# TestBench_rev2.net
KiCad netlist of a schematic drawn in EAGLE
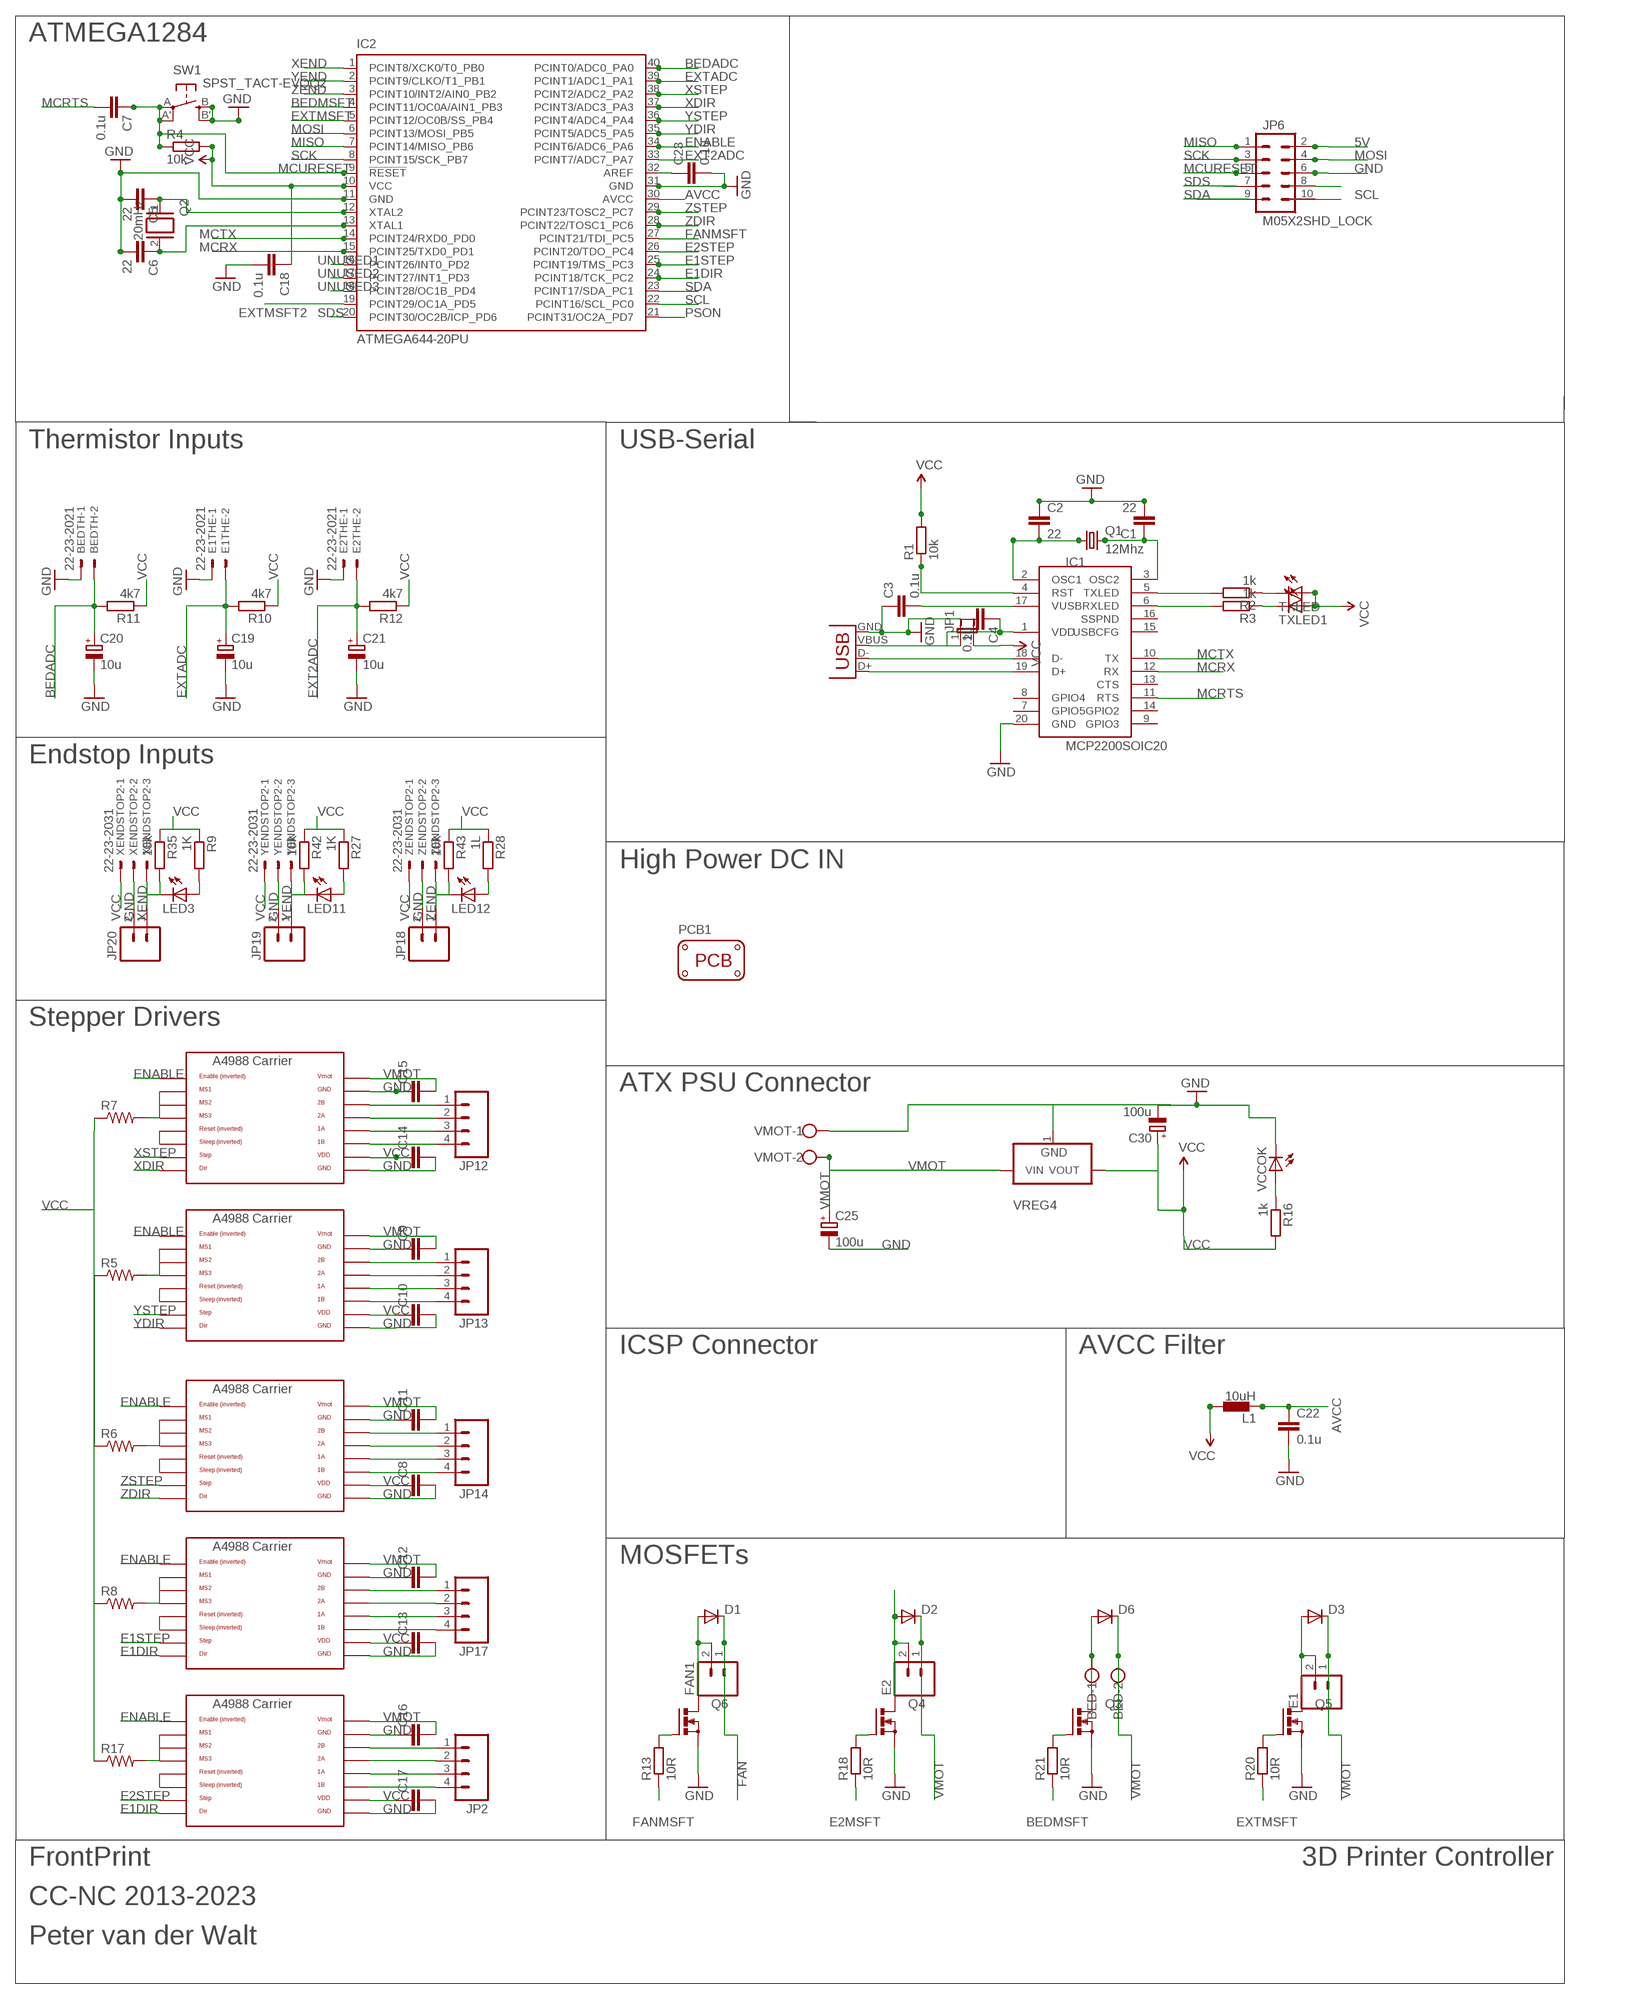
[diagram p0: schematic, sheet 1]

(export (version "E")
  (design (tool "Eeschema 10.0.6"))
  (components
    (comp (ref "BED")
      (value "W237-102")
      (footprint "eagle-import:W237-102")
      (fields (field (name "MPN") "237-102"))
      (libsource (lib "eagle-import") (part "W237-102"))
    )
    (comp (ref "BEDTH")
      (value "22-23-2021")
      (footprint "eagle-import:22-23-2021")
      (fields (field (name "MF") "MOLEX"))
      (libsource (lib "eagle-import") (part "22-23-2021"))
    )
    (comp (ref "C1")
      (value "22")
      (footprint "eagle-import:1206")
      (libsource (lib "eagle-import") (part "CAP1206"))
    )
    (comp (ref "C2")
      (value "22")
      (footprint "eagle-import:1206")
      (libsource (lib "eagle-import") (part "CAP1206"))
    )
    (comp (ref "C3")
      (value "0.1u")
      (footprint "eagle-import:1206")
      (libsource (lib "eagle-import") (part "CAP1206"))
    )
    (comp (ref "C4")
      (value "0.1u")
      (footprint "eagle-import:1206")
      (libsource (lib "eagle-import") (part "CAP1206"))
    )
    (comp (ref "C5")
      (value "22")
      (footprint "eagle-import:1206")
      (libsource (lib "eagle-import") (part "CAP1206"))
    )
    (comp (ref "C6")
      (value "22")
      (footprint "eagle-import:1206")
      (libsource (lib "eagle-import") (part "CAP1206"))
    )
    (comp (ref "C7")
      (value "0.1u")
      (footprint "eagle-import:1206")
      (libsource (lib "eagle-import") (part "CAP1206"))
    )
    (comp (ref "C8")
      (value "CAP1206")
      (footprint "eagle-import:1206")
      (libsource (lib "eagle-import") (part "CAP1206"))
    )
    (comp (ref "C9")
      (value "CAP1206")
      (footprint "eagle-import:1206")
      (libsource (lib "eagle-import") (part "CAP1206"))
    )
    (comp (ref "C10")
      (value "CAP1206")
      (footprint "eagle-import:1206")
      (libsource (lib "eagle-import") (part "CAP1206"))
    )
    (comp (ref "C11")
      (value "CAP1206")
      (footprint "eagle-import:1206")
      (libsource (lib "eagle-import") (part "CAP1206"))
    )
    (comp (ref "C12")
      (value "CAP1206")
      (footprint "eagle-import:1206")
      (libsource (lib "eagle-import") (part "CAP1206"))
    )
    (comp (ref "C13")
      (value "CAP1206")
      (footprint "eagle-import:1206")
      (libsource (lib "eagle-import") (part "CAP1206"))
    )
    (comp (ref "C14")
      (value "CAP1206")
      (footprint "eagle-import:1206")
      (libsource (lib "eagle-import") (part "CAP1206"))
    )
    (comp (ref "C15")
      (value "CAP1206")
      (footprint "eagle-import:1206")
      (libsource (lib "eagle-import") (part "CAP1206"))
    )
    (comp (ref "C16")
      (value "CAP1206")
      (footprint "eagle-import:1206")
      (libsource (lib "eagle-import") (part "CAP1206"))
    )
    (comp (ref "C17")
      (value "CAP1206")
      (footprint "eagle-import:1206")
      (libsource (lib "eagle-import") (part "CAP1206"))
    )
    (comp (ref "C18")
      (value "0.1u")
      (footprint "eagle-import:1206")
      (libsource (lib "eagle-import") (part "CAP1206"))
    )
    (comp (ref "C19")
      (value "10u")
      (footprint "eagle-import:E2,5-5")
      (libsource (lib "eagle-import") (part "CPOL-EUE2.5-5"))
    )
    (comp (ref "C20")
      (value "10u")
      (footprint "eagle-import:E2,5-5")
      (libsource (lib "eagle-import") (part "CPOL-EUE2.5-5"))
    )
    (comp (ref "C21")
      (value "10u")
      (footprint "eagle-import:E2,5-5")
      (libsource (lib "eagle-import") (part "CPOL-EUE2.5-5"))
    )
    (comp (ref "C22")
      (value "0.1u")
      (footprint "eagle-import:1206")
      (libsource (lib "eagle-import") (part "CAP1206"))
    )
    (comp (ref "C23")
      (value "0.1u")
      (footprint "eagle-import:1206")
      (libsource (lib "eagle-import") (part "CAP1206"))
    )
    (comp (ref "C25")
      (value "100u")
      (footprint "eagle-import:E5-8,5")
      (libsource (lib "eagle-import") (part "CPOL-EUE5-8.5"))
    )
    (comp (ref "C30")
      (value "100u")
      (footprint "eagle-import:E5-8,5")
      (libsource (lib "eagle-import") (part "CPOL-EUE5-8.5"))
    )
    (comp (ref "D1")
      (value "DIODE1N4148")
      (footprint "eagle-import:DIODE-1N4148")
      (libsource (lib "eagle-import") (part "DIODE1N4148"))
    )
    (comp (ref "D2")
      (value "DIODE1N4148")
      (footprint "eagle-import:DIODE-1N4148")
      (libsource (lib "eagle-import") (part "DIODE1N4148"))
    )
    (comp (ref "D3")
      (value "DIODE1N4148")
      (footprint "eagle-import:DIODE-1N4148")
      (libsource (lib "eagle-import") (part "DIODE1N4148"))
    )
    (comp (ref "D6")
      (value "DIODE1N4148")
      (footprint "eagle-import:DIODE-1N4148")
      (libsource (lib "eagle-import") (part "DIODE1N4148"))
    )
    (comp (ref "E1")
      (value "M023.5MM")
      (footprint "eagle-import:SCREWTERMINAL-3.5MM-2")
      (libsource (lib "eagle-import") (part "M023.5MM"))
    )
    (comp (ref "E1POL")
      (value "POLOLU_A4983CARRIER")
      (footprint "eagle-import:A4988BREAKOUT")
      (libsource (lib "eagle-import") (part "POLOLU_A4983CARRIER"))
    )
    (comp (ref "E1THE")
      (value "22-23-2021")
      (footprint "eagle-import:22-23-2021")
      (fields (field (name "MF") "MOLEX"))
      (libsource (lib "eagle-import") (part "22-23-2021"))
    )
    (comp (ref "E2")
      (value "M023.5MM")
      (footprint "eagle-import:SCREWTERMINAL-3.5MM-2")
      (libsource (lib "eagle-import") (part "M023.5MM"))
    )
    (comp (ref "E2POL")
      (value "POLOLU_A4983CARRIER")
      (footprint "eagle-import:A4988BREAKOUT")
      (libsource (lib "eagle-import") (part "POLOLU_A4983CARRIER"))
    )
    (comp (ref "E2THE")
      (value "22-23-2021")
      (footprint "eagle-import:22-23-2021")
      (fields (field (name "MF") "MOLEX"))
      (libsource (lib "eagle-import") (part "22-23-2021"))
    )
    (comp (ref "FAN1")
      (value "M023.5MM")
      (footprint "eagle-import:SCREWTERMINAL-3.5MM-2")
      (libsource (lib "eagle-import") (part "M023.5MM"))
    )
    (comp (ref "IC1")
      (value "MCP2200SOIC20")
      (footprint "eagle-import:SOIC20")
      (libsource (lib "eagle-import") (part "MCP2200SOIC20"))
    )
    (comp (ref "IC2")
      (value "ATMEGA644-20PU")
      (footprint "eagle-import:DIL40")
      (libsource (lib "eagle-import") (part "ATMEGA644-PU20"))
    )
    (comp (ref "JP1")
      (value "JUMPER-2PTH_LOCK")
      (footprint "eagle-import:1X02_LOCK")
      (libsource (lib "eagle-import") (part "JUMPER-2PTH_LOCK"))
    )
    (comp (ref "JP2")
      (value "M04SCREW")
      (footprint "eagle-import:SCREWTERMINAL-3.5MM-4")
      (libsource (lib "eagle-import") (part "M04SCREW"))
    )
    (comp (ref "JP6")
      (value "M05X2SHD_LOCK")
      (footprint "eagle-import:2X5-SHROUDED_LOCK")
      (libsource (lib "eagle-import") (part "M05X2SHD_LOCK"))
    )
    (comp (ref "JP12")
      (value "M04SCREW")
      (footprint "eagle-import:SCREWTERMINAL-3.5MM-4")
      (libsource (lib "eagle-import") (part "M04SCREW"))
    )
    (comp (ref "JP13")
      (value "M04SCREW")
      (footprint "eagle-import:SCREWTERMINAL-3.5MM-4")
      (libsource (lib "eagle-import") (part "M04SCREW"))
    )
    (comp (ref "JP14")
      (value "M04SCREW")
      (footprint "eagle-import:SCREWTERMINAL-3.5MM-4")
      (libsource (lib "eagle-import") (part "M04SCREW"))
    )
    (comp (ref "JP17")
      (value "M04SCREW")
      (footprint "eagle-import:SCREWTERMINAL-3.5MM-4")
      (libsource (lib "eagle-import") (part "M04SCREW"))
    )
    (comp (ref "JP18")
      (value "M023.5MM")
      (footprint "eagle-import:SCREWTERMINAL-3.5MM-2")
      (libsource (lib "eagle-import") (part "M023.5MM"))
    )
    (comp (ref "JP19")
      (value "M023.5MM")
      (footprint "eagle-import:SCREWTERMINAL-3.5MM-2")
      (libsource (lib "eagle-import") (part "M023.5MM"))
    )
    (comp (ref "JP20")
      (value "M023.5MM")
      (footprint "eagle-import:SCREWTERMINAL-3.5MM-2")
      (libsource (lib "eagle-import") (part "M023.5MM"))
    )
    (comp (ref "L1")
      (value "10uH")
      (footprint "eagle-import:BL01RN1A")
      (libsource (lib "eagle-import") (part "BL01RN1A"))
    )
    (comp (ref "LED3")
      (value "LEDCHIPLED_1206")
      (footprint "eagle-import:CHIPLED_1206")
      (libsource (lib "eagle-import") (part "LEDCHIPLED_1206"))
    )
    (comp (ref "LED11")
      (value "LEDCHIPLED_1206")
      (footprint "eagle-import:CHIPLED_1206")
      (libsource (lib "eagle-import") (part "LEDCHIPLED_1206"))
    )
    (comp (ref "LED12")
      (value "LEDCHIPLED_1206")
      (footprint "eagle-import:CHIPLED_1206")
      (libsource (lib "eagle-import") (part "LEDCHIPLED_1206"))
    )
    (comp (ref "PCB1")
      (value "PCB_DP_SQUARE-10X10")
      (footprint "eagle-import:DP100100_V1")
      (libsource (lib "eagle-import") (part "PCB_DP_SQUARE-10X10"))
    )
    (comp (ref "Q1")
      (value "12Mhz")
      (footprint "eagle-import:HC49UP")
      (libsource (lib "eagle-import") (part "CRYSTALHC49UP"))
    )
    (comp (ref "Q2")
      (value "20mHz")
      (footprint "eagle-import:QS")
      (libsource (lib "eagle-import") (part "XTAL/S"))
    )
    (comp (ref "Q3")
      (value "PMOSFET_NTO220BV")
      (footprint "eagle-import:TO220BV")
      (libsource (lib "eagle-import") (part "PMOSFET_NTO220BV"))
    )
    (comp (ref "Q4")
      (value "PMOSFET_NTO220BV")
      (footprint "eagle-import:TO220BV")
      (libsource (lib "eagle-import") (part "PMOSFET_NTO220BV"))
    )
    (comp (ref "Q5")
      (value "PMOSFET_NTO220BV")
      (footprint "eagle-import:TO220BV")
      (libsource (lib "eagle-import") (part "PMOSFET_NTO220BV"))
    )
    (comp (ref "Q6")
      (value "PMOSFET_NTO220BV")
      (footprint "eagle-import:TO220BV")
      (libsource (lib "eagle-import") (part "PMOSFET_NTO220BV"))
    )
    (comp (ref "R1")
      (value "10k")
      (footprint "eagle-import:M1206")
      (libsource (lib "eagle-import") (part "R-EU_M1206"))
    )
    (comp (ref "R2")
      (value "1k")
      (footprint "eagle-import:M1206")
      (libsource (lib "eagle-import") (part "R-EU_M1206"))
    )
    (comp (ref "R3")
      (value "1k")
      (footprint "eagle-import:M1206")
      (libsource (lib "eagle-import") (part "R-EU_M1206"))
    )
    (comp (ref "R4")
      (value "10k")
      (footprint "eagle-import:M1206")
      (libsource (lib "eagle-import") (part "R-EU_M1206"))
    )
    (comp (ref "R5")
      (value "RESISTOR1206")
      (footprint "eagle-import:1206")
      (libsource (lib "eagle-import") (part "RESISTOR1206"))
    )
    (comp (ref "R6")
      (value "RESISTOR1206")
      (footprint "eagle-import:1206")
      (libsource (lib "eagle-import") (part "RESISTOR1206"))
    )
    (comp (ref "R7")
      (value "RESISTOR1206")
      (footprint "eagle-import:1206")
      (libsource (lib "eagle-import") (part "RESISTOR1206"))
    )
    (comp (ref "R8")
      (value "RESISTOR1206")
      (footprint "eagle-import:1206")
      (libsource (lib "eagle-import") (part "RESISTOR1206"))
    )
    (comp (ref "R9")
      (value "1K")
      (footprint "eagle-import:M1206")
      (libsource (lib "eagle-import") (part "R-EU_M1206"))
    )
    (comp (ref "R10")
      (value "4k7")
      (footprint "eagle-import:M1206")
      (libsource (lib "eagle-import") (part "R-EU_M1206"))
    )
    (comp (ref "R11")
      (value "4k7")
      (footprint "eagle-import:M1206")
      (libsource (lib "eagle-import") (part "R-EU_M1206"))
    )
    (comp (ref "R12")
      (value "4k7")
      (footprint "eagle-import:M1206")
      (libsource (lib "eagle-import") (part "R-EU_M1206"))
    )
    (comp (ref "R13")
      (value "10R")
      (footprint "eagle-import:M1206")
      (libsource (lib "eagle-import") (part "R-EU_M1206"))
    )
    (comp (ref "R16")
      (value "1k")
      (footprint "eagle-import:M1206")
      (libsource (lib "eagle-import") (part "R-EU_M1206"))
    )
    (comp (ref "R17")
      (value "RESISTOR1206")
      (footprint "eagle-import:1206")
      (libsource (lib "eagle-import") (part "RESISTOR1206"))
    )
    (comp (ref "R18")
      (value "10R")
      (footprint "eagle-import:M1206")
      (libsource (lib "eagle-import") (part "R-EU_M1206"))
    )
    (comp (ref "R20")
      (value "10R")
      (footprint "eagle-import:M1206")
      (libsource (lib "eagle-import") (part "R-EU_M1206"))
    )
    (comp (ref "R21")
      (value "10R")
      (footprint "eagle-import:M1206")
      (libsource (lib "eagle-import") (part "R-EU_M1206"))
    )
    (comp (ref "R27")
      (value "1K")
      (footprint "eagle-import:M1206")
      (libsource (lib "eagle-import") (part "R-EU_M1206"))
    )
    (comp (ref "R28")
      (value "1L")
      (footprint "eagle-import:M1206")
      (libsource (lib "eagle-import") (part "R-EU_M1206"))
    )
    (comp (ref "R35")
      (value "10k")
      (footprint "eagle-import:M1206")
      (libsource (lib "eagle-import") (part "R-EU_M1206"))
    )
    (comp (ref "R42")
      (value "10k")
      (footprint "eagle-import:M1206")
      (libsource (lib "eagle-import") (part "R-EU_M1206"))
    )
    (comp (ref "R43")
      (value "10k")
      (footprint "eagle-import:M1206")
      (libsource (lib "eagle-import") (part "R-EU_M1206"))
    )
    (comp (ref "SW1")
      (value "SPST_TACT-EVQQ2")
      (footprint "eagle-import:EVQ-Q2")
      (libsource (lib "eagle-import") (part "SPST_TACT-EVQQ2"))
    )
    (comp (ref "TXLED")
      (value "LEDSMT1206")
      (footprint "eagle-import:1206")
      (libsource (lib "eagle-import") (part "LEDSMT1206"))
    )
    (comp (ref "TXLED1")
      (value "LEDSMT1206")
      (footprint "eagle-import:1206")
      (libsource (lib "eagle-import") (part "LEDSMT1206"))
    )
    (comp (ref "VCCOK")
      (value "LEDSMT1206")
      (footprint "eagle-import:1206")
      (libsource (lib "eagle-import") (part "LEDSMT1206"))
    )
    (comp (ref "VMOT")
      (value "W237-102")
      (footprint "eagle-import:W237-102")
      (fields
        (field (name "MPN") "237-102")
        (field (name "MPN_1") "237-102")
        (field (name "OC_FARNELL") "unknown")
        (field (name "OC_NEWARK") "70K9898")
      )
      (libsource (lib "eagle-import") (part "W237-102"))
    )
    (comp (ref "VREG4")
      (value "VREG_3PINS-DPAK")
      (footprint "eagle-import:DPAK")
      (libsource (lib "eagle-import") (part "VREG_3PINS-DPAK"))
    )
    (comp (ref "X1")
      (value "USBPTH")
      (footprint "eagle-import:USB-B-PTH")
      (libsource (lib "eagle-import") (part "USBPTH"))
    )
    (comp (ref "XENDSTOP2")
      (value "22-23-2031")
      (footprint "eagle-import:22-23-2031")
      (fields (field (name "MF") "MOLEX"))
      (libsource (lib "eagle-import") (part "22-23-2031"))
    )
    (comp (ref "XPOL")
      (value "POLOLU_A4983CARRIER")
      (footprint "eagle-import:A4988BREAKOUT")
      (libsource (lib "eagle-import") (part "POLOLU_A4983CARRIER"))
    )
    (comp (ref "YENDSTOP2")
      (value "22-23-2031")
      (footprint "eagle-import:22-23-2031")
      (fields (field (name "MF") "MOLEX"))
      (libsource (lib "eagle-import") (part "22-23-2031"))
    )
    (comp (ref "YPOL")
      (value "POLOLU_A4983CARRIER")
      (footprint "eagle-import:A4988BREAKOUT")
      (libsource (lib "eagle-import") (part "POLOLU_A4983CARRIER"))
    )
    (comp (ref "ZENDSTOP2")
      (value "22-23-2031")
      (footprint "eagle-import:22-23-2031")
      (fields (field (name "MF") "MOLEX"))
      (libsource (lib "eagle-import") (part "22-23-2031"))
    )
    (comp (ref "ZPOL")
      (value "POLOLU_A4983CARRIER")
      (footprint "eagle-import:A4988BREAKOUT")
      (libsource (lib "eagle-import") (part "POLOLU_A4983CARRIER"))
    )
  )
  (nets
    (net (code "1") (name "/5V") (class "Default")
      (node (ref "JP6") (pin "2") (pinfunction "2_2") (pintype "passive"))
    )
    (net (code "2") (name "/AVCC") (class "Default")
      (node (ref "C22") (pin "1") (pinfunction "1_1") (pintype "passive"))
      (node (ref "IC2") (pin "30") (pinfunction "AVCC_30") (pintype "power_in"))
      (node (ref "L1") (pin "1") (pinfunction "1_1") (pintype "passive"))
    )
    (net (code "3") (name "/BEDADC") (class "Default")
      (node (ref "BEDTH") (pin "2") (pinfunction "S_2") (pintype "passive"))
      (node (ref "C20") (pin "+") (pinfunction "+_+") (pintype "passive"))
      (node (ref "IC2") (pin "40") (pinfunction "PCINT0/ADC0_PA0_40") (pintype "bidirectional"))
      (node (ref "R11") (pin "2") (pinfunction "2_2") (pintype "passive"))
    )
    (net (code "4") (name "/BEDMSFT") (class "Default")
      (node (ref "IC2") (pin "4") (pinfunction "PCINT11/OC0A/AIN1_PB3_4") (pintype "bidirectional"))
      (node (ref "R21") (pin "1") (pinfunction "1_1") (pintype "passive"))
    )
    (net (code "5") (name "/E1DIR") (class "Default")
      (node (ref "E1POL") (pin "DIR") (pinfunction "DIR_DIR") (pintype "input"))
      (node (ref "E2POL") (pin "DIR") (pinfunction "DIR_DIR") (pintype "input"))
      (node (ref "IC2") (pin "24") (pinfunction "PCINT18/TCK_PC2_24") (pintype "bidirectional"))
    )
    (net (code "6") (name "/E1STEP") (class "Default")
      (node (ref "E1POL") (pin "STEP") (pinfunction "STEP_STEP") (pintype "input"))
      (node (ref "IC2") (pin "25") (pinfunction "PCINT19/TMS_PC3_25") (pintype "bidirectional"))
    )
    (net (code "7") (name "/E2MSFT") (class "Default")
      (node (ref "R18") (pin "1") (pinfunction "1_1") (pintype "passive"))
    )
    (net (code "8") (name "/E2STEP") (class "Default")
      (node (ref "E2POL") (pin "STEP") (pinfunction "STEP_STEP") (pintype "input"))
      (node (ref "IC2") (pin "26") (pinfunction "PCINT20/TDO_PC4_26") (pintype "bidirectional"))
    )
    (net (code "9") (name "/ENABLE") (class "Default")
      (node (ref "E1POL") (pin "EN") (pinfunction "EN_EN") (pintype "input"))
      (node (ref "E2POL") (pin "EN") (pinfunction "EN_EN") (pintype "input"))
      (node (ref "IC2") (pin "34") (pinfunction "PCINT6/ADC6_PA6_34") (pintype "bidirectional"))
      (node (ref "XPOL") (pin "EN") (pinfunction "EN_EN") (pintype "input"))
      (node (ref "YPOL") (pin "EN") (pinfunction "EN_EN") (pintype "input"))
      (node (ref "ZPOL") (pin "EN") (pinfunction "EN_EN") (pintype "input"))
    )
    (net (code "10") (name "/EXT2ADC") (class "Default")
      (node (ref "C21") (pin "+") (pinfunction "+_+") (pintype "passive"))
      (node (ref "E2THE") (pin "2") (pinfunction "S_2") (pintype "passive"))
      (node (ref "IC2") (pin "33") (pinfunction "PCINT7/ADC7_PA7_33") (pintype "bidirectional"))
      (node (ref "R12") (pin "2") (pinfunction "2_2") (pintype "passive"))
    )
    (net (code "11") (name "/EXTADC") (class "Default")
      (node (ref "C19") (pin "+") (pinfunction "+_+") (pintype "passive"))
      (node (ref "E1THE") (pin "2") (pinfunction "S_2") (pintype "passive"))
      (node (ref "IC2") (pin "39") (pinfunction "PCINT1/ADC1_PA1_39") (pintype "bidirectional"))
      (node (ref "R10") (pin "2") (pinfunction "2_2") (pintype "passive"))
    )
    (net (code "12") (name "/EXTMSFT") (class "Default")
      (node (ref "IC2") (pin "5") (pinfunction "PCINT12/OC0B/SS_PB4_5") (pintype "bidirectional"))
      (node (ref "R20") (pin "1") (pinfunction "1_1") (pintype "passive"))
    )
    (net (code "13") (name "/EXTMSFT2") (class "Default")
      (node (ref "IC2") (pin "19") (pinfunction "PCINT29/OC1A_PD5_19") (pintype "bidirectional"))
    )
    (net (code "14") (name "/FAN") (class "Default")
      (node (ref "D1") (pin "C") (pinfunction "C_C") (pintype "passive"))
      (node (ref "FAN1") (pin "1") (pinfunction "1_1") (pintype "passive"))
    )
    (net (code "15") (name "/FANMSFT") (class "Default")
      (node (ref "IC2") (pin "27") (pinfunction "PCINT21/TDI_PC5_27") (pintype "bidirectional"))
      (node (ref "R13") (pin "1") (pinfunction "1_1") (pintype "passive"))
    )
    (net (code "16") (name "/MCRTS") (class "Default")
      (node (ref "C7") (pin "2") (pinfunction "2_2") (pintype "passive"))
      (node (ref "IC1") (pin "11") (pinfunction "RTS_11") (pintype "bidirectional"))
    )
    (net (code "17") (name "/MCRX") (class "Default")
      (node (ref "IC1") (pin "12") (pinfunction "RX_12") (pintype "bidirectional"))
      (node (ref "IC2") (pin "15") (pinfunction "PCINT25/TXD0_PD1_15") (pintype "bidirectional"))
    )
    (net (code "18") (name "/MCTX") (class "Default")
      (node (ref "IC1") (pin "10") (pinfunction "TX_10") (pintype "bidirectional"))
      (node (ref "IC2") (pin "14") (pinfunction "PCINT24/RXD0_PD0_14") (pintype "bidirectional"))
    )
    (net (code "19") (name "/MCURESET") (class "Default")
      (node (ref "C7") (pin "1") (pinfunction "1_1") (pintype "passive"))
      (node (ref "IC2") (pin "9") (pinfunction "~{RESET}_9") (pintype "input"))
      (node (ref "JP6") (pin "5") (pinfunction "5_5") (pintype "passive"))
      (node (ref "R4") (pin "1") (pinfunction "1_1") (pintype "passive"))
      (node (ref "SW1") (pin "A") (pinfunction "P_A") (pintype "passive"))
      (node (ref "SW1") (pin "A'") (pinfunction "P1_A'") (pintype "passive"))
    )
    (net (code "20") (name "/MISO") (class "Default")
      (node (ref "IC2") (pin "7") (pinfunction "PCINT14/MISO_PB6_7") (pintype "bidirectional"))
      (node (ref "JP6") (pin "1") (pinfunction "1_1") (pintype "passive"))
    )
    (net (code "21") (name "/MOSI") (class "Default")
      (node (ref "IC2") (pin "6") (pinfunction "PCINT13/MOSI_PB5_6") (pintype "bidirectional"))
      (node (ref "JP6") (pin "4") (pinfunction "4_4") (pintype "passive"))
    )
    (net (code "22") (name "/PSON") (class "Default")
      (node (ref "IC2") (pin "21") (pinfunction "PCINT31/OC2A_PD7_21") (pintype "bidirectional"))
    )
    (net (code "23") (name "/SCK") (class "Default")
      (node (ref "IC2") (pin "8") (pinfunction "PCINT15/SCK_PB7_8") (pintype "bidirectional"))
      (node (ref "JP6") (pin "3") (pinfunction "3_3") (pintype "passive"))
    )
    (net (code "24") (name "/SCL") (class "Default")
      (node (ref "IC2") (pin "22") (pinfunction "PCINT16/SCL_PC0_22") (pintype "bidirectional"))
      (node (ref "JP6") (pin "10") (pinfunction "10_10") (pintype "passive"))
    )
    (net (code "25") (name "/SDA") (class "Default")
      (node (ref "IC2") (pin "23") (pinfunction "PCINT17/SDA_PC1_23") (pintype "bidirectional"))
      (node (ref "JP6") (pin "9") (pinfunction "9_9") (pintype "passive"))
    )
    (net (code "26") (name "/SDS") (class "Default")
      (node (ref "IC2") (pin "20") (pinfunction "PCINT30/OC2B/ICP_PD6_20") (pintype "bidirectional"))
      (node (ref "JP6") (pin "7") (pinfunction "7_7") (pintype "passive"))
    )
    (net (code "27") (name "/UNUSED1") (class "Default")
      (node (ref "IC2") (pin "16") (pinfunction "PCINT26/INT0_PD2_16") (pintype "bidirectional"))
    )
    (net (code "28") (name "/UNUSED2") (class "Default")
      (node (ref "IC2") (pin "17") (pinfunction "PCINT27/INT1_PD3_17") (pintype "bidirectional"))
    )
    (net (code "29") (name "/UNUSED3") (class "Default")
      (node (ref "IC2") (pin "18") (pinfunction "PCINT28/OC1B_PD4_18") (pintype "bidirectional"))
    )
    (net (code "30") (name "/VMOT") (class "Default")
      (node (ref "BED") (pin "2") (pinfunction "KL_2") (pintype "passive"))
      (node (ref "C11") (pin "2") (pinfunction "2_2") (pintype "passive"))
      (node (ref "C12") (pin "2") (pinfunction "2_2") (pintype "passive"))
      (node (ref "C15") (pin "2") (pinfunction "2_2") (pintype "passive"))
      (node (ref "C16") (pin "2") (pinfunction "2_2") (pintype "passive"))
      (node (ref "C25") (pin "+") (pinfunction "+_+") (pintype "passive"))
      (node (ref "C9") (pin "2") (pinfunction "2_2") (pintype "passive"))
      (node (ref "D2") (pin "C") (pinfunction "C_C") (pintype "passive"))
      (node (ref "D3") (pin "C") (pinfunction "C_C") (pintype "passive"))
      (node (ref "D6") (pin "C") (pinfunction "C_C") (pintype "passive"))
      (node (ref "E1") (pin "1") (pinfunction "1_1") (pintype "passive"))
      (node (ref "E1POL") (pin "VMOT") (pinfunction "VMOT_VMOT") (pintype "power_in"))
      (node (ref "E2") (pin "1") (pinfunction "1_1") (pintype "passive"))
      (node (ref "E2POL") (pin "VMOT") (pinfunction "VMOT_VMOT") (pintype "power_in"))
      (node (ref "VMOT") (pin "2") (pinfunction "KL_2") (pintype "passive"))
      (node (ref "VREG4") (pin "3") (pinfunction "VIN_3") (pintype "bidirectional"))
      (node (ref "XPOL") (pin "VMOT") (pinfunction "VMOT_VMOT") (pintype "power_in"))
      (node (ref "YPOL") (pin "VMOT") (pinfunction "VMOT_VMOT") (pintype "power_in"))
      (node (ref "ZPOL") (pin "VMOT") (pinfunction "VMOT_VMOT") (pintype "power_in"))
    )
    (net (code "31") (name "/XDIR") (class "Default")
      (node (ref "IC2") (pin "37") (pinfunction "PCINT3/ADC3_PA3_37") (pintype "bidirectional"))
      (node (ref "XPOL") (pin "DIR") (pinfunction "DIR_DIR") (pintype "input"))
    )
    (net (code "32") (name "/XEND") (class "Default")
      (node (ref "IC2") (pin "1") (pinfunction "PCINT8/XCK0/T0_PB0_1") (pintype "bidirectional"))
      (node (ref "JP20") (pin "1") (pinfunction "1_1") (pintype "passive"))
      (node (ref "LED3") (pin "C") (pinfunction "C_C") (pintype "passive"))
      (node (ref "R35") (pin "2") (pinfunction "2_2") (pintype "passive"))
      (node (ref "XENDSTOP2") (pin "3") (pinfunction "S_3") (pintype "passive"))
    )
    (net (code "33") (name "/XSTEP") (class "Default")
      (node (ref "IC2") (pin "38") (pinfunction "PCINT2/ADC2_PA2_38") (pintype "bidirectional"))
      (node (ref "XPOL") (pin "STEP") (pinfunction "STEP_STEP") (pintype "input"))
    )
    (net (code "34") (name "/YDIR") (class "Default")
      (node (ref "IC2") (pin "35") (pinfunction "PCINT5/ADC5_PA5_35") (pintype "bidirectional"))
      (node (ref "YPOL") (pin "DIR") (pinfunction "DIR_DIR") (pintype "input"))
    )
    (net (code "35") (name "/YEND") (class "Default")
      (node (ref "IC2") (pin "2") (pinfunction "PCINT9/CLKO/T1_PB1_2") (pintype "bidirectional"))
      (node (ref "JP19") (pin "1") (pinfunction "1_1") (pintype "passive"))
      (node (ref "LED11") (pin "C") (pinfunction "C_C") (pintype "passive"))
      (node (ref "R42") (pin "2") (pinfunction "2_2") (pintype "passive"))
      (node (ref "YENDSTOP2") (pin "3") (pinfunction "S_3") (pintype "passive"))
    )
    (net (code "36") (name "/YSTEP") (class "Default")
      (node (ref "IC2") (pin "36") (pinfunction "PCINT4/ADC4_PA4_36") (pintype "bidirectional"))
      (node (ref "YPOL") (pin "STEP") (pinfunction "STEP_STEP") (pintype "input"))
    )
    (net (code "37") (name "/ZDIR") (class "Default")
      (node (ref "IC2") (pin "28") (pinfunction "PCINT22/TOSC1_PC6_28") (pintype "bidirectional"))
      (node (ref "ZPOL") (pin "DIR") (pinfunction "DIR_DIR") (pintype "input"))
    )
    (net (code "38") (name "/ZEND") (class "Default")
      (node (ref "IC2") (pin "3") (pinfunction "PCINT10/INT2/AIN0_PB2_3") (pintype "bidirectional"))
      (node (ref "JP18") (pin "1") (pinfunction "1_1") (pintype "passive"))
      (node (ref "LED12") (pin "C") (pinfunction "C_C") (pintype "passive"))
      (node (ref "R43") (pin "2") (pinfunction "2_2") (pintype "passive"))
      (node (ref "ZENDSTOP2") (pin "3") (pinfunction "S_3") (pintype "passive"))
    )
    (net (code "39") (name "/ZSTEP") (class "Default")
      (node (ref "IC2") (pin "29") (pinfunction "PCINT23/TOSC2_PC7_29") (pintype "bidirectional"))
      (node (ref "ZPOL") (pin "STEP") (pinfunction "STEP_STEP") (pintype "input"))
    )
    (net (code "40") (name "GND") (class "Default")
      (node (ref "BEDTH") (pin "1") (pinfunction "S_1") (pintype "passive"))
      (node (ref "C1") (pin "2") (pinfunction "2_2") (pintype "passive"))
      (node (ref "C10") (pin "2") (pinfunction "2_2") (pintype "passive"))
      (node (ref "C11") (pin "1") (pinfunction "1_1") (pintype "passive"))
      (node (ref "C12") (pin "1") (pinfunction "1_1") (pintype "passive"))
      (node (ref "C13") (pin "2") (pinfunction "2_2") (pintype "passive"))
      (node (ref "C14") (pin "2") (pinfunction "2_2") (pintype "passive"))
      (node (ref "C15") (pin "1") (pinfunction "1_1") (pintype "passive"))
      (node (ref "C16") (pin "1") (pinfunction "1_1") (pintype "passive"))
      (node (ref "C17") (pin "2") (pinfunction "2_2") (pintype "passive"))
      (node (ref "C18") (pin "2") (pinfunction "2_2") (pintype "passive"))
      (node (ref "C19") (pin "-") (pinfunction "-_-") (pintype "passive"))
      (node (ref "C2") (pin "1") (pinfunction "1_1") (pintype "passive"))
      (node (ref "C20") (pin "-") (pinfunction "-_-") (pintype "passive"))
      (node (ref "C21") (pin "-") (pinfunction "-_-") (pintype "passive"))
      (node (ref "C22") (pin "2") (pinfunction "2_2") (pintype "passive"))
      (node (ref "C23") (pin "2") (pinfunction "2_2") (pintype "passive"))
      (node (ref "C25") (pin "-") (pinfunction "-_-") (pintype "passive"))
      (node (ref "C3") (pin "1") (pinfunction "1_1") (pintype "passive"))
      (node (ref "C30") (pin "-") (pinfunction "-_-") (pintype "passive"))
      (node (ref "C4") (pin "2") (pinfunction "2_2") (pintype "passive"))
      (node (ref "C5") (pin "2") (pinfunction "2_2") (pintype "passive"))
      (node (ref "C6") (pin "2") (pinfunction "2_2") (pintype "passive"))
      (node (ref "C8") (pin "2") (pinfunction "2_2") (pintype "passive"))
      (node (ref "C9") (pin "1") (pinfunction "1_1") (pintype "passive"))
      (node (ref "E1POL") (pin "GND") (pinfunction "GND_GND") (pintype "power_in"))
      (node (ref "E1POL") (pin "GND@0") (pinfunction "GND_GND@0") (pintype "power_in"))
      (node (ref "E1THE") (pin "1") (pinfunction "S_1") (pintype "passive"))
      (node (ref "E2POL") (pin "GND") (pinfunction "GND_GND") (pintype "power_in"))
      (node (ref "E2POL") (pin "GND@0") (pinfunction "GND_GND@0") (pintype "power_in"))
      (node (ref "E2THE") (pin "1") (pinfunction "S_1") (pintype "passive"))
      (node (ref "IC1") (pin "20") (pinfunction "GND_20") (pintype "bidirectional"))
      (node (ref "IC2") (pin "11") (pinfunction "GND_11") (pintype "power_in"))
      (node (ref "IC2") (pin "31") (pinfunction "GND_31") (pintype "power_in"))
      (node (ref "JP18") (pin "2") (pinfunction "2_2") (pintype "passive"))
      (node (ref "JP19") (pin "2") (pinfunction "2_2") (pintype "passive"))
      (node (ref "JP20") (pin "2") (pinfunction "2_2") (pintype "passive"))
      (node (ref "JP6") (pin "6") (pinfunction "6_6") (pintype "passive"))
      (node (ref "Q3") (pin "S") (pinfunction "S_S") (pintype "passive"))
      (node (ref "Q4") (pin "S") (pinfunction "S_S") (pintype "passive"))
      (node (ref "Q5") (pin "S") (pinfunction "S_S") (pintype "passive"))
      (node (ref "Q6") (pin "S") (pinfunction "S_S") (pintype "passive"))
      (node (ref "SW1") (pin "B") (pinfunction "S_B") (pintype "passive"))
      (node (ref "SW1") (pin "B'") (pinfunction "S1_B'") (pintype "passive"))
      (node (ref "VCCOK") (pin "C") (pinfunction "C_C") (pintype "passive"))
      (node (ref "VMOT") (pin "1") (pinfunction "KL_1") (pintype "passive"))
      (node (ref "VREG4") (pin "1") (pinfunction "GND_1") (pintype "bidirectional"))
      (node (ref "X1") (pin "GND") (pinfunction "GND_GND") (pintype "bidirectional"))
      (node (ref "XENDSTOP2") (pin "2") (pinfunction "S_2") (pintype "passive"))
      (node (ref "XPOL") (pin "GND") (pinfunction "GND_GND") (pintype "power_in"))
      (node (ref "XPOL") (pin "GND@0") (pinfunction "GND_GND@0") (pintype "power_in"))
      (node (ref "YENDSTOP2") (pin "2") (pinfunction "S_2") (pintype "passive"))
      (node (ref "YPOL") (pin "GND") (pinfunction "GND_GND") (pintype "power_in"))
      (node (ref "YPOL") (pin "GND@0") (pinfunction "GND_GND@0") (pintype "power_in"))
      (node (ref "ZENDSTOP2") (pin "2") (pinfunction "S_2") (pintype "passive"))
      (node (ref "ZPOL") (pin "GND") (pinfunction "GND_GND") (pintype "power_in"))
      (node (ref "ZPOL") (pin "GND@0") (pinfunction "GND_GND@0") (pintype "power_in"))
    )
    (net (code "41") (name "Net-(BEDA-KL)") (class "Default")
      (node (ref "BED") (pin "1") (pinfunction "KL_1") (pintype "passive"))
      (node (ref "D6") (pin "A") (pinfunction "A_A") (pintype "passive"))
      (node (ref "Q3") (pin "D") (pinfunction "D_D") (pintype "passive"))
    )
    (net (code "42") (name "Net-(D1-PadA)") (class "Default")
      (node (ref "D1") (pin "A") (pinfunction "A_A") (pintype "passive"))
      (node (ref "FAN1") (pin "2") (pinfunction "2_2") (pintype "passive"))
      (node (ref "Q6") (pin "D") (pinfunction "D_D") (pintype "passive"))
    )
    (net (code "43") (name "Net-(D2-PadA)") (class "Default")
      (node (ref "D2") (pin "A") (pinfunction "A_A") (pintype "passive"))
      (node (ref "E2") (pin "2") (pinfunction "2_2") (pintype "passive"))
      (node (ref "Q4") (pin "D") (pinfunction "D_D") (pintype "passive"))
    )
    (net (code "44") (name "Net-(D3-PadA)") (class "Default")
      (node (ref "D3") (pin "A") (pinfunction "A_A") (pintype "passive"))
      (node (ref "E1") (pin "2") (pinfunction "2_2") (pintype "passive"))
      (node (ref "Q5") (pin "D") (pinfunction "D_D") (pintype "passive"))
    )
    (net (code "45") (name "Net-(E1POL-Pad1A)") (class "Default")
      (node (ref "E1POL") (pin "1A") (pinfunction "1A_1A") (pintype "output"))
      (node (ref "JP17") (pin "3") (pinfunction "3_3") (pintype "passive"))
    )
    (net (code "46") (name "Net-(E1POL-Pad1B)") (class "Default")
      (node (ref "E1POL") (pin "1B") (pinfunction "1B_1B") (pintype "output"))
      (node (ref "JP17") (pin "4") (pinfunction "4_4") (pintype "passive"))
    )
    (net (code "47") (name "Net-(E1POL-Pad2A)") (class "Default")
      (node (ref "E1POL") (pin "2A") (pinfunction "2A_2A") (pintype "output"))
      (node (ref "JP17") (pin "2") (pinfunction "2_2") (pintype "passive"))
    )
    (net (code "48") (name "Net-(E1POL-Pad2B)") (class "Default")
      (node (ref "E1POL") (pin "2B") (pinfunction "2B_2B") (pintype "output"))
      (node (ref "JP17") (pin "1") (pinfunction "1_1") (pintype "passive"))
    )
    (net (code "49") (name "Net-(E1POL-PadMS1)") (class "Default")
      (node (ref "E1POL") (pin "MS1") (pinfunction "MS1_MS1") (pintype "input"))
      (node (ref "E1POL") (pin "MS2") (pinfunction "MS2_MS2") (pintype "input"))
      (node (ref "E1POL") (pin "MS3") (pinfunction "MS3_MS3") (pintype "input"))
      (node (ref "R8") (pin "2") (pinfunction "2_2") (pintype "passive"))
    )
    (net (code "50") (name "Net-(E1POL-SLEEP)") (class "Default")
      (node (ref "E1POL") (pin "RST") (pinfunction "RST_RST") (pintype "input"))
      (node (ref "E1POL") (pin "SLP") (pinfunction "SLEEP_SLP") (pintype "input"))
    )
    (net (code "51") (name "Net-(E2POL-Pad1A)") (class "Default")
      (node (ref "E2POL") (pin "1A") (pinfunction "1A_1A") (pintype "output"))
      (node (ref "JP2") (pin "3") (pinfunction "3_3") (pintype "passive"))
    )
    (net (code "52") (name "Net-(E2POL-Pad1B)") (class "Default")
      (node (ref "E2POL") (pin "1B") (pinfunction "1B_1B") (pintype "output"))
      (node (ref "JP2") (pin "4") (pinfunction "4_4") (pintype "passive"))
    )
    (net (code "53") (name "Net-(E2POL-Pad2A)") (class "Default")
      (node (ref "E2POL") (pin "2A") (pinfunction "2A_2A") (pintype "output"))
      (node (ref "JP2") (pin "2") (pinfunction "2_2") (pintype "passive"))
    )
    (net (code "54") (name "Net-(E2POL-Pad2B)") (class "Default")
      (node (ref "E2POL") (pin "2B") (pinfunction "2B_2B") (pintype "output"))
      (node (ref "JP2") (pin "1") (pinfunction "1_1") (pintype "passive"))
    )
    (net (code "55") (name "Net-(E2POL-PadMS1)") (class "Default")
      (node (ref "E2POL") (pin "MS1") (pinfunction "MS1_MS1") (pintype "input"))
      (node (ref "E2POL") (pin "MS2") (pinfunction "MS2_MS2") (pintype "input"))
      (node (ref "E2POL") (pin "MS3") (pinfunction "MS3_MS3") (pintype "input"))
      (node (ref "R17") (pin "2") (pinfunction "2_2") (pintype "passive"))
    )
    (net (code "56") (name "Net-(E2POL-SLEEP)") (class "Default")
      (node (ref "E2POL") (pin "RST") (pinfunction "RST_RST") (pintype "input"))
      (node (ref "E2POL") (pin "SLP") (pinfunction "SLEEP_SLP") (pintype "input"))
    )
    (net (code "57") (name "Net-(IC1-D+)") (class "Default")
      (node (ref "IC1") (pin "19") (pinfunction "D+_19") (pintype "bidirectional"))
      (node (ref "X1") (pin "D+") (pinfunction "D+_D+") (pintype "bidirectional"))
    )
    (net (code "58") (name "Net-(IC1-D-)") (class "Default")
      (node (ref "IC1") (pin "18") (pinfunction "D-_18") (pintype "bidirectional"))
      (node (ref "X1") (pin "D-") (pinfunction "D-_D-") (pintype "bidirectional"))
    )
    (net (code "59") (name "Net-(IC1-OSC1)") (class "Default")
      (node (ref "C2") (pin "2") (pinfunction "2_2") (pintype "passive"))
      (node (ref "IC1") (pin "2") (pinfunction "OSC1_2") (pintype "bidirectional"))
      (node (ref "Q1") (pin "1") (pinfunction "1_1") (pintype "passive"))
    )
    (net (code "60") (name "Net-(IC1-OSC2)") (class "Default")
      (node (ref "C1") (pin "1") (pinfunction "1_1") (pintype "passive"))
      (node (ref "IC1") (pin "3") (pinfunction "OSC2_3") (pintype "bidirectional"))
      (node (ref "Q1") (pin "2") (pinfunction "2_2") (pintype "passive"))
    )
    (net (code "61") (name "Net-(IC1-RST)") (class "Default")
      (node (ref "IC1") (pin "4") (pinfunction "RST_4") (pintype "bidirectional"))
      (node (ref "R1") (pin "1") (pinfunction "1_1") (pintype "passive"))
    )
    (net (code "62") (name "Net-(IC1-RXLED)") (class "Default")
      (node (ref "IC1") (pin "6") (pinfunction "RXLED_6") (pintype "bidirectional"))
      (node (ref "R3") (pin "2") (pinfunction "2_2") (pintype "passive"))
    )
    (net (code "63") (name "Net-(IC1-TXLED)") (class "Default")
      (node (ref "IC1") (pin "5") (pinfunction "TXLED_5") (pintype "bidirectional"))
      (node (ref "R2") (pin "2") (pinfunction "2_2") (pintype "passive"))
    )
    (net (code "64") (name "Net-(IC1-VDD)") (class "Default")
      (node (ref "C4") (pin "1") (pinfunction "1_1") (pintype "passive"))
      (node (ref "IC1") (pin "1") (pinfunction "VDD_1") (pintype "bidirectional"))
      (node (ref "JP1") (pin "1") (pinfunction "1_1") (pintype "passive"))
      (node (ref "X1") (pin "VBUS") (pinfunction "VBUS_VBUS") (pintype "bidirectional"))
    )
    (net (code "65") (name "Net-(IC1-VUSB)") (class "Default")
      (node (ref "C3") (pin "2") (pinfunction "2_2") (pintype "passive"))
      (node (ref "IC1") (pin "17") (pinfunction "VUSB_17") (pintype "bidirectional"))
    )
    (net (code "66") (name "Net-(IC2-AREF)") (class "Default")
      (node (ref "C23") (pin "1") (pinfunction "1_1") (pintype "passive"))
      (node (ref "IC2") (pin "32") (pinfunction "AREF_32") (pintype "passive"))
    )
    (net (code "67") (name "Net-(IC2-XTAL1)") (class "Default")
      (node (ref "C6") (pin "1") (pinfunction "1_1") (pintype "passive"))
      (node (ref "IC2") (pin "13") (pinfunction "XTAL1_13") (pintype "input"))
      (node (ref "Q2") (pin "2") (pinfunction "2_2") (pintype "passive"))
    )
    (net (code "68") (name "Net-(IC2-XTAL2)") (class "Default")
      (node (ref "C5") (pin "1") (pinfunction "1_1") (pintype "passive"))
      (node (ref "IC2") (pin "12") (pinfunction "XTAL2_12") (pintype "output"))
      (node (ref "Q2") (pin "1") (pinfunction "1_1") (pintype "passive"))
    )
    (net (code "69") (name "Net-(JP12-Pad1)") (class "Default")
      (node (ref "JP12") (pin "1") (pinfunction "1_1") (pintype "passive"))
      (node (ref "XPOL") (pin "2B") (pinfunction "2B_2B") (pintype "output"))
    )
    (net (code "70") (name "Net-(JP12-Pad2)") (class "Default")
      (node (ref "JP12") (pin "2") (pinfunction "2_2") (pintype "passive"))
      (node (ref "XPOL") (pin "2A") (pinfunction "2A_2A") (pintype "output"))
    )
    (net (code "71") (name "Net-(JP12-Pad3)") (class "Default")
      (node (ref "JP12") (pin "3") (pinfunction "3_3") (pintype "passive"))
      (node (ref "XPOL") (pin "1A") (pinfunction "1A_1A") (pintype "output"))
    )
    (net (code "72") (name "Net-(JP12-Pad4)") (class "Default")
      (node (ref "JP12") (pin "4") (pinfunction "4_4") (pintype "passive"))
      (node (ref "XPOL") (pin "1B") (pinfunction "1B_1B") (pintype "output"))
    )
    (net (code "73") (name "Net-(JP13-Pad1)") (class "Default")
      (node (ref "JP13") (pin "1") (pinfunction "1_1") (pintype "passive"))
      (node (ref "YPOL") (pin "2B") (pinfunction "2B_2B") (pintype "output"))
    )
    (net (code "74") (name "Net-(JP13-Pad2)") (class "Default")
      (node (ref "JP13") (pin "2") (pinfunction "2_2") (pintype "passive"))
      (node (ref "YPOL") (pin "2A") (pinfunction "2A_2A") (pintype "output"))
    )
    (net (code "75") (name "Net-(JP13-Pad3)") (class "Default")
      (node (ref "JP13") (pin "3") (pinfunction "3_3") (pintype "passive"))
      (node (ref "YPOL") (pin "1A") (pinfunction "1A_1A") (pintype "output"))
    )
    (net (code "76") (name "Net-(JP13-Pad4)") (class "Default")
      (node (ref "JP13") (pin "4") (pinfunction "4_4") (pintype "passive"))
      (node (ref "YPOL") (pin "1B") (pinfunction "1B_1B") (pintype "output"))
    )
    (net (code "77") (name "Net-(JP14-Pad1)") (class "Default")
      (node (ref "JP14") (pin "1") (pinfunction "1_1") (pintype "passive"))
      (node (ref "ZPOL") (pin "2B") (pinfunction "2B_2B") (pintype "output"))
    )
    (net (code "78") (name "Net-(JP14-Pad2)") (class "Default")
      (node (ref "JP14") (pin "2") (pinfunction "2_2") (pintype "passive"))
      (node (ref "ZPOL") (pin "2A") (pinfunction "2A_2A") (pintype "output"))
    )
    (net (code "79") (name "Net-(JP14-Pad3)") (class "Default")
      (node (ref "JP14") (pin "3") (pinfunction "3_3") (pintype "passive"))
      (node (ref "ZPOL") (pin "1A") (pinfunction "1A_1A") (pintype "output"))
    )
    (net (code "80") (name "Net-(JP14-Pad4)") (class "Default")
      (node (ref "JP14") (pin "4") (pinfunction "4_4") (pintype "passive"))
      (node (ref "ZPOL") (pin "1B") (pinfunction "1B_1B") (pintype "output"))
    )
    (net (code "81") (name "Net-(LED3-PadA)") (class "Default")
      (node (ref "LED3") (pin "A") (pinfunction "A_A") (pintype "passive"))
      (node (ref "R9") (pin "2") (pinfunction "2_2") (pintype "passive"))
    )
    (net (code "82") (name "Net-(LED11-PadA)") (class "Default")
      (node (ref "LED11") (pin "A") (pinfunction "A_A") (pintype "passive"))
      (node (ref "R27") (pin "2") (pinfunction "2_2") (pintype "passive"))
    )
    (net (code "83") (name "Net-(LED12-PadA)") (class "Default")
      (node (ref "LED12") (pin "A") (pinfunction "A_A") (pintype "passive"))
      (node (ref "R28") (pin "2") (pinfunction "2_2") (pintype "passive"))
    )
    (net (code "84") (name "Net-(Q3-PadG)") (class "Default")
      (node (ref "Q3") (pin "G") (pinfunction "G_G") (pintype "passive"))
      (node (ref "R21") (pin "2") (pinfunction "2_2") (pintype "passive"))
    )
    (net (code "85") (name "Net-(Q4-PadG)") (class "Default")
      (node (ref "Q4") (pin "G") (pinfunction "G_G") (pintype "passive"))
      (node (ref "R18") (pin "2") (pinfunction "2_2") (pintype "passive"))
    )
    (net (code "86") (name "Net-(Q5-PadG)") (class "Default")
      (node (ref "Q5") (pin "G") (pinfunction "G_G") (pintype "passive"))
      (node (ref "R20") (pin "2") (pinfunction "2_2") (pintype "passive"))
    )
    (net (code "87") (name "Net-(Q6-PadG)") (class "Default")
      (node (ref "Q6") (pin "G") (pinfunction "G_G") (pintype "passive"))
      (node (ref "R13") (pin "2") (pinfunction "2_2") (pintype "passive"))
    )
    (net (code "88") (name "Net-(R2-Pad1)") (class "Default")
      (node (ref "R2") (pin "1") (pinfunction "1_1") (pintype "passive"))
      (node (ref "TXLED") (pin "C") (pinfunction "C_C") (pintype "passive"))
    )
    (net (code "89") (name "Net-(R3-Pad1)") (class "Default")
      (node (ref "R3") (pin "1") (pinfunction "1_1") (pintype "passive"))
      (node (ref "TXLED1") (pin "C") (pinfunction "C_C") (pintype "passive"))
    )
    (net (code "90") (name "Net-(R5-Pad2)") (class "Default")
      (node (ref "R5") (pin "2") (pinfunction "2_2") (pintype "passive"))
      (node (ref "YPOL") (pin "MS1") (pinfunction "MS1_MS1") (pintype "input"))
      (node (ref "YPOL") (pin "MS2") (pinfunction "MS2_MS2") (pintype "input"))
      (node (ref "YPOL") (pin "MS3") (pinfunction "MS3_MS3") (pintype "input"))
    )
    (net (code "91") (name "Net-(R6-Pad2)") (class "Default")
      (node (ref "R6") (pin "2") (pinfunction "2_2") (pintype "passive"))
      (node (ref "ZPOL") (pin "MS1") (pinfunction "MS1_MS1") (pintype "input"))
      (node (ref "ZPOL") (pin "MS2") (pinfunction "MS2_MS2") (pintype "input"))
      (node (ref "ZPOL") (pin "MS3") (pinfunction "MS3_MS3") (pintype "input"))
    )
    (net (code "92") (name "Net-(R7-Pad2)") (class "Default")
      (node (ref "R7") (pin "2") (pinfunction "2_2") (pintype "passive"))
      (node (ref "XPOL") (pin "MS1") (pinfunction "MS1_MS1") (pintype "input"))
      (node (ref "XPOL") (pin "MS2") (pinfunction "MS2_MS2") (pintype "input"))
      (node (ref "XPOL") (pin "MS3") (pinfunction "MS3_MS3") (pintype "input"))
    )
    (net (code "93") (name "Net-(R16-Pad1)") (class "Default")
      (node (ref "R16") (pin "1") (pinfunction "1_1") (pintype "passive"))
      (node (ref "VCCOK") (pin "A") (pinfunction "A_A") (pintype "passive"))
    )
    (net (code "94") (name "Net-(XPOL-SLEEP)") (class "Default")
      (node (ref "XPOL") (pin "RST") (pinfunction "RST_RST") (pintype "input"))
      (node (ref "XPOL") (pin "SLP") (pinfunction "SLEEP_SLP") (pintype "input"))
    )
    (net (code "95") (name "Net-(YPOL-SLEEP)") (class "Default")
      (node (ref "YPOL") (pin "RST") (pinfunction "RST_RST") (pintype "input"))
      (node (ref "YPOL") (pin "SLP") (pinfunction "SLEEP_SLP") (pintype "input"))
    )
    (net (code "96") (name "Net-(ZPOL-SLEEP)") (class "Default")
      (node (ref "ZPOL") (pin "RST") (pinfunction "RST_RST") (pintype "input"))
      (node (ref "ZPOL") (pin "SLP") (pinfunction "SLEEP_SLP") (pintype "input"))
    )
    (net (code "97") (name "VCC") (class "Default")
      (node (ref "C10") (pin "1") (pinfunction "1_1") (pintype "passive"))
      (node (ref "C13") (pin "1") (pinfunction "1_1") (pintype "passive"))
      (node (ref "C14") (pin "1") (pinfunction "1_1") (pintype "passive"))
      (node (ref "C17") (pin "1") (pinfunction "1_1") (pintype "passive"))
      (node (ref "C18") (pin "1") (pinfunction "1_1") (pintype "passive"))
      (node (ref "C30") (pin "+") (pinfunction "+_+") (pintype "passive"))
      (node (ref "C8") (pin "1") (pinfunction "1_1") (pintype "passive"))
      (node (ref "E1POL") (pin "VDD") (pinfunction "VDD_VDD") (pintype "power_in"))
      (node (ref "E2POL") (pin "VDD") (pinfunction "VDD_VDD") (pintype "power_in"))
      (node (ref "IC2") (pin "10") (pinfunction "VCC_10") (pintype "power_in"))
      (node (ref "JP1") (pin "2") (pinfunction "2_2") (pintype "passive"))
      (node (ref "L1") (pin "2") (pinfunction "2_2") (pintype "passive"))
      (node (ref "R1") (pin "2") (pinfunction "2_2") (pintype "passive"))
      (node (ref "R10") (pin "1") (pinfunction "1_1") (pintype "passive"))
      (node (ref "R11") (pin "1") (pinfunction "1_1") (pintype "passive"))
      (node (ref "R12") (pin "1") (pinfunction "1_1") (pintype "passive"))
      (node (ref "R16") (pin "2") (pinfunction "2_2") (pintype "passive"))
      (node (ref "R17") (pin "1") (pinfunction "1_1") (pintype "passive"))
      (node (ref "R27") (pin "1") (pinfunction "1_1") (pintype "passive"))
      (node (ref "R28") (pin "1") (pinfunction "1_1") (pintype "passive"))
      (node (ref "R35") (pin "1") (pinfunction "1_1") (pintype "passive"))
      (node (ref "R4") (pin "2") (pinfunction "2_2") (pintype "passive"))
      (node (ref "R42") (pin "1") (pinfunction "1_1") (pintype "passive"))
      (node (ref "R43") (pin "1") (pinfunction "1_1") (pintype "passive"))
      (node (ref "R5") (pin "1") (pinfunction "1_1") (pintype "passive"))
      (node (ref "R6") (pin "1") (pinfunction "1_1") (pintype "passive"))
      (node (ref "R7") (pin "1") (pinfunction "1_1") (pintype "passive"))
      (node (ref "R8") (pin "1") (pinfunction "1_1") (pintype "passive"))
      (node (ref "R9") (pin "1") (pinfunction "1_1") (pintype "passive"))
      (node (ref "TXLED") (pin "A") (pinfunction "A_A") (pintype "passive"))
      (node (ref "TXLED1") (pin "A") (pinfunction "A_A") (pintype "passive"))
      (node (ref "VREG4") (pin "2") (pinfunction "VOUT_2") (pintype "bidirectional"))
      (node (ref "XENDSTOP2") (pin "1") (pinfunction "S_1") (pintype "passive"))
      (node (ref "XPOL") (pin "VDD") (pinfunction "VDD_VDD") (pintype "power_in"))
      (node (ref "YENDSTOP2") (pin "1") (pinfunction "S_1") (pintype "passive"))
      (node (ref "YPOL") (pin "VDD") (pinfunction "VDD_VDD") (pintype "power_in"))
      (node (ref "ZENDSTOP2") (pin "1") (pinfunction "S_1") (pintype "passive"))
      (node (ref "ZPOL") (pin "VDD") (pinfunction "VDD_VDD") (pintype "power_in"))
    )
    (net (code "98") (name "unconnected-(IC1-CTS-Pad13)") (class "Default")
      (node (ref "IC1") (pin "13") (pinfunction "CTS_13") (pintype "bidirectional"))
    )
    (net (code "99") (name "unconnected-(IC1-GPIO2-Pad14)") (class "Default")
      (node (ref "IC1") (pin "14") (pinfunction "GPIO2_14") (pintype "bidirectional"))
    )
    (net (code "100") (name "unconnected-(IC1-GPIO3-Pad9)") (class "Default")
      (node (ref "IC1") (pin "9") (pinfunction "GPIO3_9") (pintype "bidirectional"))
    )
    (net (code "101") (name "unconnected-(IC1-GPIO4-Pad8)") (class "Default")
      (node (ref "IC1") (pin "8") (pinfunction "GPIO4_8") (pintype "bidirectional"))
    )
    (net (code "102") (name "unconnected-(IC1-GPIO5-Pad7)") (class "Default")
      (node (ref "IC1") (pin "7") (pinfunction "GPIO5_7") (pintype "bidirectional"))
    )
    (net (code "103") (name "unconnected-(IC1-SSPND-Pad16)") (class "Default")
      (node (ref "IC1") (pin "16") (pinfunction "SSPND_16") (pintype "bidirectional"))
    )
    (net (code "104") (name "unconnected-(IC1-USBCFG-Pad15)") (class "Default")
      (node (ref "IC1") (pin "15") (pinfunction "USBCFG_15") (pintype "bidirectional"))
    )
    (net (code "105") (name "unconnected-(JP6-Pad8)") (class "Default")
      (node (ref "JP6") (pin "8") (pinfunction "8_8") (pintype "passive"))
    )
  )
)
